# node.net
KiCad netlist of a schematic drawn in Altium Designer
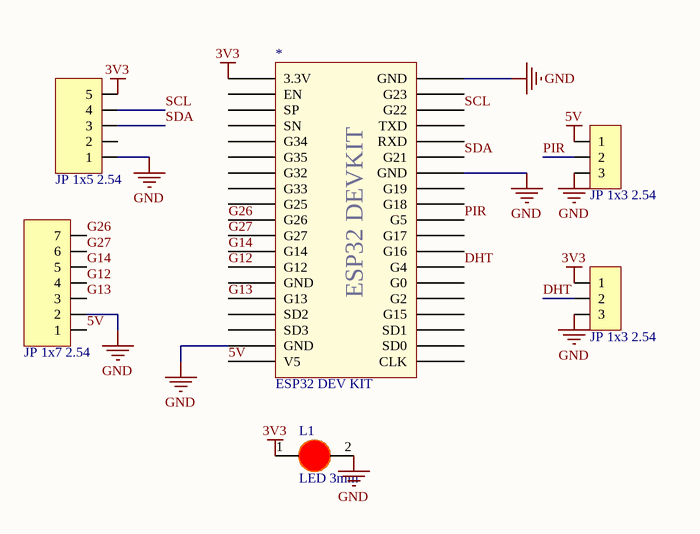
[diagram p0: node.SchDoc]

(export (version "E")
  (design (tool "Eeschema 10.0.6"))
  (components
    (comp (ref "*")
      (value "ESP32 DEV KIT")
      (footprint "ESP32 DEVKIT")
      (libsource (lib "Altium_Lib_by_KhueNguyenCreator") (part "ESP32 DEV KIT"))
    )
    (comp (ref "JP1")
      (value "JP 1x3 2.54")
      (footprint "JP 1x3 DT")
      (description "Cắm")
      (libsource (lib "OCVITTV") (part "JP 1x3 2.54 Duc Thang"))
    )
    (comp (ref "JP2")
      (value "JP 1x5 2.54")
      (footprint "JP 1x5 CT")
      (description "Cắm")
      (libsource (lib "OCVITTV") (part "JP 1x5 2.54 Cai Thang"))
    )
    (comp (ref "JP3")
      (value "JP 1x3 2.54")
      (footprint "JP 1x3 DT")
      (description "Cắm")
      (libsource (lib "OCVITTV") (part "JP 1x3 2.54 Duc Thang"))
    )
    (comp (ref "JP4")
      (value "JP 1x7 2.54")
      (footprint "JP 1x7 CT")
      (description "Cắm")
      (libsource (lib "Altium_Lib_by_KhueNguyenCreator") (part "JP 1x7 2.54 Cai Thang"))
    )
    (comp (ref "L1")
      (value "LED 3mm")
      (footprint "LED-3MM-RED")
      (description "Cắm")
      (libsource (lib "OCVITTV") (part "LED 3mm Do"))
    )
  )
  (nets
    (net (code "1") (name "/DHT") (class "Default")
      (node (ref "*") (pin "26") (pinfunction "G4_26") (pintype "passive"))
      (node (ref "JP3") (pin "2") (pinfunction "2_2") (pintype "passive"))
    )
    (net (code "2") (name "/G12") (class "Default")
      (node (ref "*") (pin "13") (pinfunction "G12_13") (pintype "passive"))
      (node (ref "JP4") (pin "4") (pinfunction "4_4") (pintype "passive"))
    )
    (net (code "3") (name "/G13") (class "Default")
      (node (ref "*") (pin "15") (pinfunction "G13_15") (pintype "passive"))
      (node (ref "JP4") (pin "3") (pinfunction "3_3") (pintype "passive"))
    )
    (net (code "4") (name "/G14") (class "Default")
      (node (ref "*") (pin "12") (pinfunction "G14_12") (pintype "passive"))
      (node (ref "JP4") (pin "5") (pinfunction "5_5") (pintype "passive"))
    )
    (net (code "5") (name "/G26") (class "Default")
      (node (ref "*") (pin "10") (pinfunction "G26_10") (pintype "passive"))
      (node (ref "JP4") (pin "7") (pinfunction "7_7") (pintype "passive"))
    )
    (net (code "6") (name "/G27") (class "Default")
      (node (ref "*") (pin "11") (pinfunction "G27_11") (pintype "passive"))
      (node (ref "JP4") (pin "6") (pinfunction "6_6") (pintype "passive"))
    )
    (net (code "7") (name "/PIR") (class "Default")
      (node (ref "*") (pin "29") (pinfunction "G5_29") (pintype "passive"))
      (node (ref "JP1") (pin "2") (pinfunction "2_2") (pintype "passive"))
    )
    (net (code "8") (name "/SCL") (class "Default")
      (node (ref "*") (pin "36") (pinfunction "G22_36") (pintype "passive"))
      (node (ref "JP2") (pin "4") (pinfunction "4_4") (pintype "passive"))
    )
    (net (code "9") (name "/SDA") (class "Default")
      (node (ref "*") (pin "33") (pinfunction "G21_33") (pintype "passive"))
      (node (ref "JP2") (pin "3") (pinfunction "3_3") (pintype "passive"))
    )
    (net (code "10") (name "3V3") (class "Default")
      (node (ref "*") (pin "1") (pinfunction "3.3V_1") (pintype "passive"))
      (node (ref "JP2") (pin "5") (pinfunction "5_5") (pintype "passive"))
      (node (ref "JP3") (pin "1") (pinfunction "1_1") (pintype "passive"))
      (node (ref "L1") (pin "1") (pinfunction "A_1") (pintype "passive"))
    )
    (net (code "11") (name "5V") (class "Default")
      (node (ref "*") (pin "19") (pinfunction "V5_19") (pintype "passive"))
      (node (ref "JP1") (pin "1") (pinfunction "1_1") (pintype "passive"))
      (node (ref "JP4") (pin "1") (pinfunction "1_1") (pintype "passive"))
    )
    (net (code "12") (name "GND") (class "Default")
      (node (ref "*") (pin "18") (pinfunction "GND_18") (pintype "passive"))
      (node (ref "*") (pin "32") (pinfunction "GND_32") (pintype "passive"))
      (node (ref "*") (pin "38") (pinfunction "GND_38") (pintype "passive"))
      (node (ref "JP1") (pin "3") (pinfunction "3_3") (pintype "passive"))
      (node (ref "JP2") (pin "1") (pinfunction "1_1") (pintype "passive"))
      (node (ref "JP3") (pin "3") (pinfunction "3_3") (pintype "passive"))
      (node (ref "JP4") (pin "2") (pinfunction "2_2") (pintype "passive"))
      (node (ref "L1") (pin "2") (pinfunction "K_2") (pintype "passive"))
    )
    (net (code "13") (name "unconnected-(*-CLK-Pad20)") (class "Default")
      (node (ref "*") (pin "20") (pinfunction "CLK_20") (pintype "passive"))
    )
    (net (code "14") (name "unconnected-(*-EN-Pad2)") (class "Default")
      (node (ref "*") (pin "2") (pinfunction "EN_2") (pintype "passive"))
    )
    (net (code "15") (name "unconnected-(*-G0-Pad25)") (class "Default")
      (node (ref "*") (pin "25") (pinfunction "G0_25") (pintype "passive"))
    )
    (net (code "16") (name "unconnected-(*-G2-Pad24)") (class "Default")
      (node (ref "*") (pin "24") (pinfunction "G2_24") (pintype "passive"))
    )
    (net (code "17") (name "unconnected-(*-G15-Pad23)") (class "Default")
      (node (ref "*") (pin "23") (pinfunction "G15_23") (pintype "passive"))
    )
    (net (code "18") (name "unconnected-(*-G16-Pad27)") (class "Default")
      (node (ref "*") (pin "27") (pinfunction "G16_27") (pintype "passive"))
    )
    (net (code "19") (name "unconnected-(*-G17-Pad28)") (class "Default")
      (node (ref "*") (pin "28") (pinfunction "G17_28") (pintype "passive"))
    )
    (net (code "20") (name "unconnected-(*-G18-Pad30)") (class "Default")
      (node (ref "*") (pin "30") (pinfunction "G18_30") (pintype "passive"))
    )
    (net (code "21") (name "unconnected-(*-G19-Pad31)") (class "Default")
      (node (ref "*") (pin "31") (pinfunction "G19_31") (pintype "passive"))
    )
    (net (code "22") (name "unconnected-(*-G23-Pad37)") (class "Default")
      (node (ref "*") (pin "37") (pinfunction "G23_37") (pintype "passive"))
    )
    (net (code "23") (name "unconnected-(*-G25-Pad9)") (class "Default")
      (node (ref "*") (pin "9") (pinfunction "G25_9") (pintype "passive"))
    )
    (net (code "24") (name "unconnected-(*-G32-Pad7)") (class "Default")
      (node (ref "*") (pin "7") (pinfunction "G32_7") (pintype "passive"))
    )
    (net (code "25") (name "unconnected-(*-G33-Pad8)") (class "Default")
      (node (ref "*") (pin "8") (pinfunction "G33_8") (pintype "passive"))
    )
    (net (code "26") (name "unconnected-(*-G34-Pad5)") (class "Default")
      (node (ref "*") (pin "5") (pinfunction "G34_5") (pintype "passive"))
    )
    (net (code "27") (name "unconnected-(*-G35-Pad6)") (class "Default")
      (node (ref "*") (pin "6") (pinfunction "G35_6") (pintype "passive"))
    )
    (net (code "28") (name "unconnected-(*-GND-Pad14)") (class "Default")
      (node (ref "*") (pin "14") (pinfunction "GND_14") (pintype "passive"))
    )
    (net (code "29") (name "unconnected-(*-RXD-Pad34)") (class "Default")
      (node (ref "*") (pin "34") (pinfunction "RXD_34") (pintype "passive"))
    )
    (net (code "30") (name "unconnected-(*-SD0-Pad21)") (class "Default")
      (node (ref "*") (pin "21") (pinfunction "SD0_21") (pintype "passive"))
    )
    (net (code "31") (name "unconnected-(*-SD1-Pad22)") (class "Default")
      (node (ref "*") (pin "22") (pinfunction "SD1_22") (pintype "passive"))
    )
    (net (code "32") (name "unconnected-(*-SD2-Pad16)") (class "Default")
      (node (ref "*") (pin "16") (pinfunction "SD2_16") (pintype "passive"))
    )
    (net (code "33") (name "unconnected-(*-SD3-Pad17)") (class "Default")
      (node (ref "*") (pin "17") (pinfunction "SD3_17") (pintype "passive"))
    )
    (net (code "34") (name "unconnected-(*-SN-Pad4)") (class "Default")
      (node (ref "*") (pin "4") (pinfunction "SN_4") (pintype "passive"))
    )
    (net (code "35") (name "unconnected-(*-SP-Pad3)") (class "Default")
      (node (ref "*") (pin "3") (pinfunction "SP_3") (pintype "passive"))
    )
    (net (code "36") (name "unconnected-(*-TXD-Pad35)") (class "Default")
      (node (ref "*") (pin "35") (pinfunction "TXD_35") (pintype "passive"))
    )
    (net (code "37") (name "unconnected-(JP2-Pad2)") (class "Default")
      (node (ref "JP2") (pin "2") (pinfunction "2_2") (pintype "passive"))
    )
  )
)
